# scale.net
KiCad netlist of a schematic drawn in EAGLE
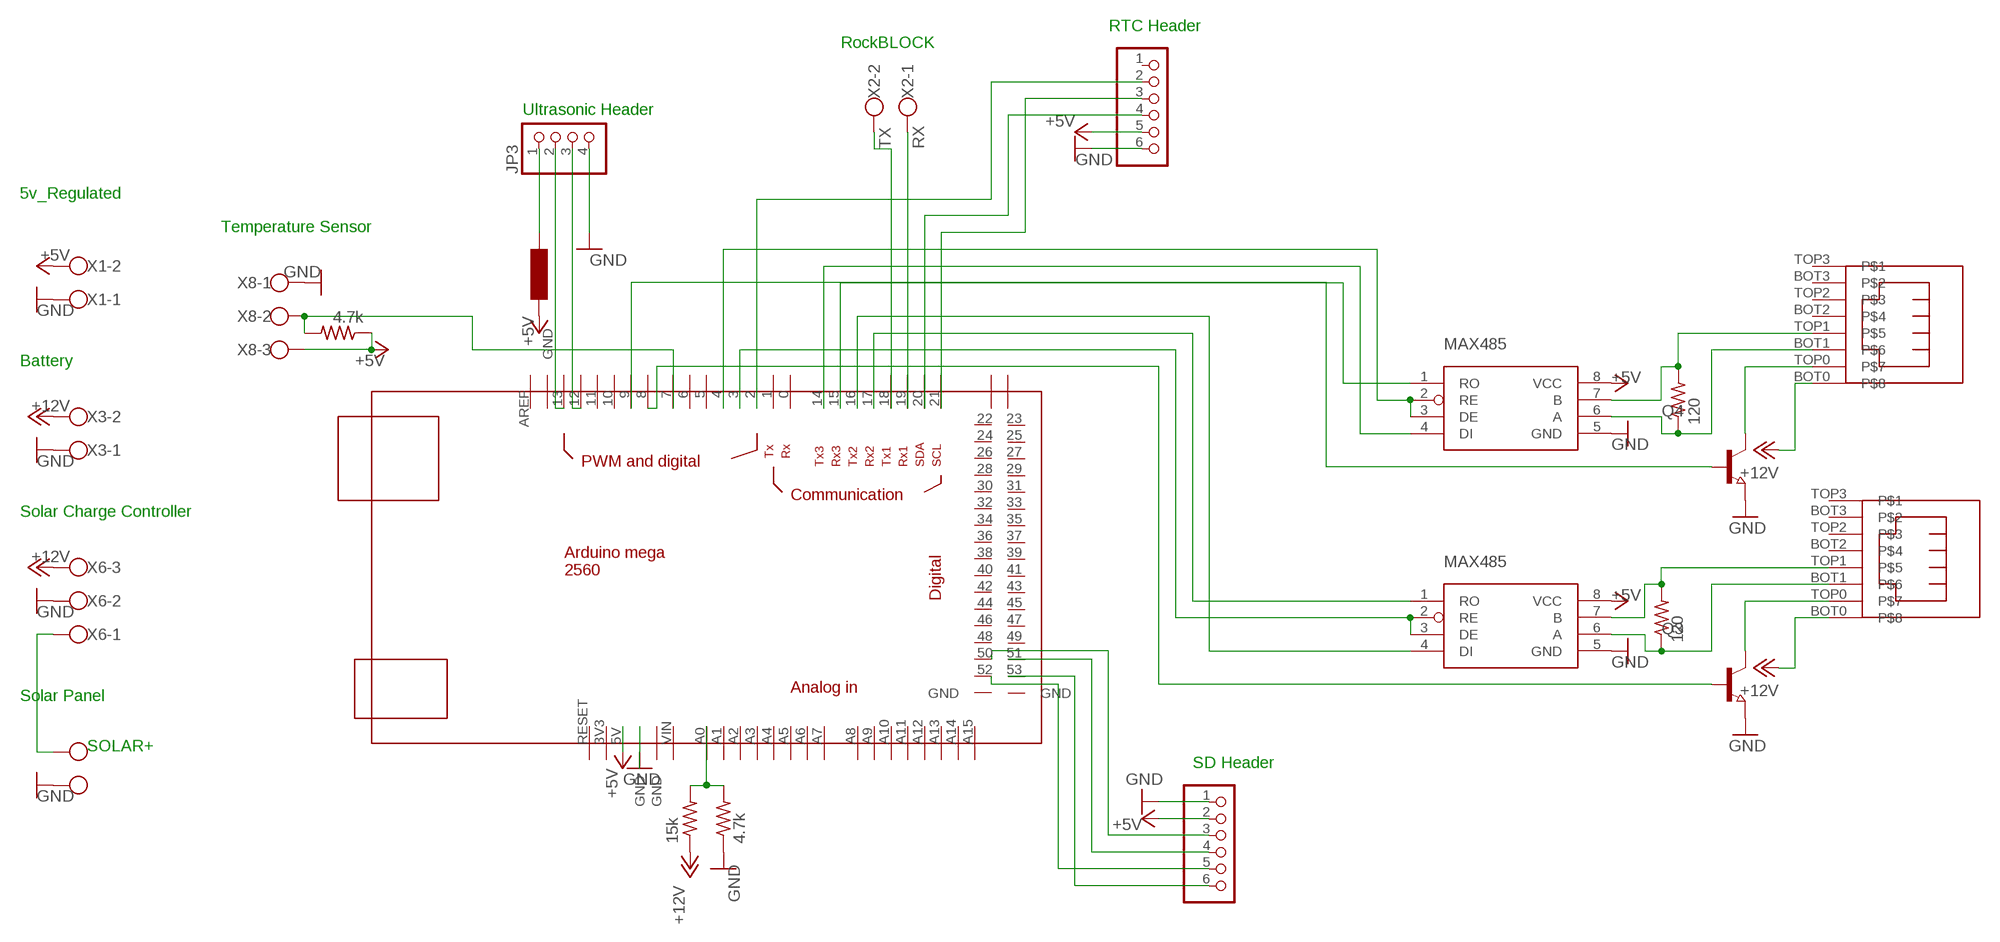
[diagram p0: schematic, sheet 1]

(export (version "E")
  (design (tool "Eeschema 10.0.6"))
  (components
    (comp (ref "JP1")
      (value "PINHD-1X6")
      (footprint "eagle-import:1X06")
      (libsource (lib "eagle-import") (part "PINHD-1X6"))
    )
    (comp (ref "JP2")
      (value "PINHD-1X6")
      (footprint "eagle-import:1X06")
      (libsource (lib "eagle-import") (part "PINHD-1X6"))
    )
    (comp (ref "JP3")
      (value "PINHD-1X4")
      (footprint "eagle-import:1X04")
      (libsource (lib "eagle-import") (part "PINHD-1X4"))
    )
    (comp (ref "JP4")
      (value "ETHERNET")
      (footprint "eagle-import:ETHERNET")
      (libsource (lib "eagle-import") (part "ETHERNET"))
    )
    (comp (ref "JP5")
      (value "ETHERNET")
      (footprint "eagle-import:ETHERNET")
      (libsource (lib "eagle-import") (part "ETHERNET"))
    )
    (comp (ref "L1")
      (value "100uH")
      (footprint "eagle-import:NLFV32T-101K-EF")
      (libsource (lib "eagle-import") (part "NLFV32T-101K-EF"))
    )
    (comp (ref "Q3")
      (value "NPN-TRANSISTOR_SOT23")
      (footprint "eagle-import:SOT23")
      (libsource (lib "eagle-import") (part "NPN-TRANSISTOR_SOT23"))
    )
    (comp (ref "Q4")
      (value "NPN-TRANSISTOR_SOT23")
      (footprint "eagle-import:SOT23")
      (libsource (lib "eagle-import") (part "NPN-TRANSISTOR_SOT23"))
    )
    (comp (ref "R1")
      (value "120")
      (footprint "eagle-import:R0805")
      (libsource (lib "eagle-import") (part "R-US_R0805"))
    )
    (comp (ref "R3")
      (value "4.7k")
      (footprint "eagle-import:R0805")
      (libsource (lib "eagle-import") (part "R-US_R0805"))
    )
    (comp (ref "R7")
      (value "120")
      (footprint "eagle-import:R0805")
      (libsource (lib "eagle-import") (part "R-US_R0805"))
    )
    (comp (ref "R8")
      (value "15k")
      (footprint "eagle-import:R0805")
      (libsource (lib "eagle-import") (part "R-US_R0805"))
    )
    (comp (ref "R9")
      (value "4.7k")
      (footprint "eagle-import:R0805")
      (libsource (lib "eagle-import") (part "R-US_R0805"))
    )
    (comp (ref "U$1")
      (value "MAX485")
      (footprint "eagle-import:SO08")
      (libsource (lib "eagle-import") (part "MAX485"))
    )
    (comp (ref "U$2")
      (value "MAX485")
      (footprint "eagle-import:SO08")
      (libsource (lib "eagle-import") (part "MAX485"))
    )
    (comp (ref "U$3")
      (value "MEGA_DEVICE")
      (footprint "eagle-import:MEGAOUTLINE")
      (libsource (lib "eagle-import") (part "MEGA_DEVICE"))
    )
    (comp (ref "X1")
      (value "W237-102")
      (footprint "eagle-import:W237-102")
      (fields (field (name "MPN") "237-102"))
      (libsource (lib "eagle-import") (part "W237-102"))
    )
    (comp (ref "X2")
      (value "W237-102")
      (footprint "eagle-import:W237-102")
      (fields (field (name "MPN") "237-102"))
      (libsource (lib "eagle-import") (part "W237-102"))
    )
    (comp (ref "X3")
      (value "W237-102")
      (footprint "eagle-import:W237-102")
      (fields (field (name "MPN") "237-102"))
      (libsource (lib "eagle-import") (part "W237-102"))
    )
    (comp (ref "X6")
      (value "W237-103")
      (footprint "eagle-import:W237-103")
      (fields (field (name "MPN") "237-103"))
      (libsource (lib "eagle-import") (part "W237-103"))
    )
    (comp (ref "X7")
      (value "W237-102")
      (footprint "eagle-import:W237-102")
      (fields (field (name "MPN") "237-102"))
      (libsource (lib "eagle-import") (part "W237-102"))
    )
    (comp (ref "X8")
      (value "W237-103")
      (footprint "eagle-import:W237-103")
      (fields (field (name "MPN") "237-103"))
      (libsource (lib "eagle-import") (part "W237-103"))
    )
  )
  (nets
    (net (code "1") (name "+5V") (class "Default")
      (node (ref "JP1") (pin "2") (pinfunction "2_2") (pintype "passive"))
      (node (ref "JP2") (pin "5") (pinfunction "5_5") (pintype "passive"))
      (node (ref "L1") (pin "P$1") (pinfunction "P$1_P$1") (pintype "bidirectional"))
      (node (ref "R3") (pin "1") (pinfunction "1_1") (pintype "passive"))
      (node (ref "U$1") (pin "8") (pinfunction "VCC_8") (pintype "bidirectional"))
      (node (ref "U$2") (pin "8") (pinfunction "VCC_8") (pintype "bidirectional"))
      (node (ref "U$3") (pin "5V") (pinfunction "5V_5V") (pintype "bidirectional"))
      (node (ref "X1") (pin "2") (pinfunction "KL_2") (pintype "passive"))
      (node (ref "X8") (pin "3") (pinfunction "KL_3") (pintype "passive"))
    )
    (net (code "2") (name "+12V") (class "Default")
      (node (ref "JP4") (pin "BOT0") (pinfunction "P$8_BOT0") (pintype "bidirectional"))
      (node (ref "JP5") (pin "BOT0") (pinfunction "P$8_BOT0") (pintype "bidirectional"))
      (node (ref "R8") (pin "1") (pinfunction "1_1") (pintype "passive"))
      (node (ref "X3") (pin "2") (pinfunction "KL_2") (pintype "passive"))
      (node (ref "X6") (pin "3") (pinfunction "KL_3") (pintype "passive"))
    )
    (net (code "3") (name "GND") (class "Default")
      (node (ref "JP1") (pin "1") (pinfunction "1_1") (pintype "passive"))
      (node (ref "JP2") (pin "6") (pinfunction "6_6") (pintype "passive"))
      (node (ref "JP3") (pin "4") (pinfunction "4_4") (pintype "passive"))
      (node (ref "Q3") (pin "2") (pinfunction "E_2") (pintype "passive"))
      (node (ref "Q4") (pin "2") (pinfunction "E_2") (pintype "passive"))
      (node (ref "R9") (pin "1") (pinfunction "1_1") (pintype "passive"))
      (node (ref "U$1") (pin "5") (pinfunction "GND_5") (pintype "bidirectional"))
      (node (ref "U$2") (pin "5") (pinfunction "GND_5") (pintype "bidirectional"))
      (node (ref "U$3") (pin "GND@2") (pinfunction "GND_GND@2") (pintype "bidirectional"))
      (node (ref "X1") (pin "1") (pinfunction "KL_1") (pintype "passive"))
      (node (ref "X3") (pin "1") (pinfunction "KL_1") (pintype "passive"))
      (node (ref "X6") (pin "2") (pinfunction "KL_2") (pintype "passive"))
      (node (ref "X7") (pin "1") (pinfunction "KL_1") (pintype "passive"))
      (node (ref "X8") (pin "1") (pinfunction "KL_1") (pintype "passive"))
    )
    (net (code "4") (name "Net-(JP1-Pad3)") (class "Default")
      (node (ref "JP1") (pin "3") (pinfunction "3_3") (pintype "passive"))
      (node (ref "U$3") (pin "50") (pinfunction "50_50") (pintype "bidirectional"))
    )
    (net (code "5") (name "Net-(JP1-Pad4)") (class "Default")
      (node (ref "JP1") (pin "4") (pinfunction "4_4") (pintype "passive"))
      (node (ref "U$3") (pin "51") (pinfunction "51_51") (pintype "bidirectional"))
    )
    (net (code "6") (name "Net-(JP1-Pad5)") (class "Default")
      (node (ref "JP1") (pin "5") (pinfunction "5_5") (pintype "passive"))
      (node (ref "U$3") (pin "52") (pinfunction "52_52") (pintype "bidirectional"))
    )
    (net (code "7") (name "Net-(JP1-Pad6)") (class "Default")
      (node (ref "JP1") (pin "6") (pinfunction "6_6") (pintype "passive"))
      (node (ref "U$3") (pin "53") (pinfunction "53_53") (pintype "bidirectional"))
    )
    (net (code "8") (name "Net-(JP2-Pad2)") (class "Default")
      (node (ref "JP2") (pin "2") (pinfunction "2_2") (pintype "passive"))
      (node (ref "U$3") (pin "2") (pinfunction "2_2") (pintype "bidirectional"))
    )
    (net (code "9") (name "Net-(JP2-Pad3)") (class "Default")
      (node (ref "JP2") (pin "3") (pinfunction "3_3") (pintype "passive"))
      (node (ref "U$3") (pin "21") (pinfunction "21_21") (pintype "bidirectional"))
    )
    (net (code "10") (name "Net-(JP2-Pad4)") (class "Default")
      (node (ref "JP2") (pin "4") (pinfunction "4_4") (pintype "passive"))
      (node (ref "U$3") (pin "20") (pinfunction "20_20") (pintype "bidirectional"))
    )
    (net (code "11") (name "Net-(JP3-Pad1)") (class "Default")
      (node (ref "JP3") (pin "1") (pinfunction "1_1") (pintype "passive"))
      (node (ref "L1") (pin "P$2") (pinfunction "P$2_P$2") (pintype "bidirectional"))
    )
    (net (code "12") (name "Net-(JP3-Pad2)") (class "Default")
      (node (ref "JP3") (pin "2") (pinfunction "2_2") (pintype "passive"))
      (node (ref "U$3") (pin "13") (pinfunction "13_13") (pintype "bidirectional"))
    )
    (net (code "13") (name "Net-(JP3-Pad3)") (class "Default")
      (node (ref "JP3") (pin "3") (pinfunction "3_3") (pintype "passive"))
      (node (ref "U$3") (pin "12") (pinfunction "12_12") (pintype "bidirectional"))
    )
    (net (code "14") (name "Net-(JP4-P$5)") (class "Default")
      (node (ref "JP4") (pin "TOP1") (pinfunction "P$5_TOP1") (pintype "bidirectional"))
      (node (ref "R1") (pin "2") (pinfunction "2_2") (pintype "passive"))
      (node (ref "U$1") (pin "7") (pinfunction "B_7") (pintype "bidirectional"))
    )
    (net (code "15") (name "Net-(JP4-P$6)") (class "Default")
      (node (ref "JP4") (pin "BOT1") (pinfunction "P$6_BOT1") (pintype "bidirectional"))
      (node (ref "R1") (pin "1") (pinfunction "1_1") (pintype "passive"))
      (node (ref "U$1") (pin "6") (pinfunction "A_6") (pintype "bidirectional"))
    )
    (net (code "16") (name "Net-(JP4-P$7)") (class "Default")
      (node (ref "JP4") (pin "TOP0") (pinfunction "P$7_TOP0") (pintype "bidirectional"))
      (node (ref "Q4") (pin "3") (pinfunction "C_3") (pintype "passive"))
    )
    (net (code "17") (name "Net-(JP5-P$5)") (class "Default")
      (node (ref "JP5") (pin "TOP1") (pinfunction "P$5_TOP1") (pintype "bidirectional"))
      (node (ref "R7") (pin "2") (pinfunction "2_2") (pintype "passive"))
      (node (ref "U$2") (pin "7") (pinfunction "B_7") (pintype "bidirectional"))
    )
    (net (code "18") (name "Net-(JP5-P$6)") (class "Default")
      (node (ref "JP5") (pin "BOT1") (pinfunction "P$6_BOT1") (pintype "bidirectional"))
      (node (ref "R7") (pin "1") (pinfunction "1_1") (pintype "passive"))
      (node (ref "U$2") (pin "6") (pinfunction "A_6") (pintype "bidirectional"))
    )
    (net (code "19") (name "Net-(JP5-P$7)") (class "Default")
      (node (ref "JP5") (pin "TOP0") (pinfunction "P$7_TOP0") (pintype "bidirectional"))
      (node (ref "Q3") (pin "3") (pinfunction "C_3") (pintype "passive"))
    )
    (net (code "20") (name "Net-(Q3-B)") (class "Default")
      (node (ref "Q3") (pin "1") (pinfunction "B_1") (pintype "passive"))
      (node (ref "U$3") (pin "8") (pinfunction "8_8") (pintype "bidirectional"))
    )
    (net (code "21") (name "Net-(Q4-B)") (class "Default")
      (node (ref "Q4") (pin "1") (pinfunction "B_1") (pintype "passive"))
      (node (ref "U$3") (pin "9") (pinfunction "9_9") (pintype "bidirectional"))
    )
    (net (code "22") (name "Net-(R8-Pad2)") (class "Default")
      (node (ref "R8") (pin "2") (pinfunction "2_2") (pintype "passive"))
      (node (ref "R9") (pin "2") (pinfunction "2_2") (pintype "passive"))
      (node (ref "U$3") (pin "A0") (pinfunction "A0_A0") (pintype "bidirectional"))
    )
    (net (code "23") (name "Net-(U$1-DE)") (class "Default")
      (node (ref "U$1") (pin "2") (pinfunction "RE_2") (pintype "bidirectional"))
      (node (ref "U$1") (pin "3") (pinfunction "DE_3") (pintype "bidirectional"))
      (node (ref "U$3") (pin "4") (pinfunction "4_4") (pintype "bidirectional"))
    )
    (net (code "24") (name "Net-(U$1-DI)") (class "Default")
      (node (ref "U$1") (pin "4") (pinfunction "DI_4") (pintype "bidirectional"))
      (node (ref "U$3") (pin "14") (pinfunction "14_14") (pintype "bidirectional"))
    )
    (net (code "25") (name "Net-(U$1-RO)") (class "Default")
      (node (ref "U$1") (pin "1") (pinfunction "RO_1") (pintype "bidirectional"))
      (node (ref "U$3") (pin "15") (pinfunction "15_15") (pintype "bidirectional"))
    )
    (net (code "26") (name "Net-(U$2-DE)") (class "Default")
      (node (ref "U$2") (pin "2") (pinfunction "RE_2") (pintype "bidirectional"))
      (node (ref "U$2") (pin "3") (pinfunction "DE_3") (pintype "bidirectional"))
      (node (ref "U$3") (pin "3") (pinfunction "3_3") (pintype "bidirectional"))
    )
    (net (code "27") (name "Net-(U$2-DI)") (class "Default")
      (node (ref "U$2") (pin "4") (pinfunction "DI_4") (pintype "bidirectional"))
      (node (ref "U$3") (pin "16") (pinfunction "16_16") (pintype "bidirectional"))
    )
    (net (code "28") (name "Net-(U$2-RO)") (class "Default")
      (node (ref "U$2") (pin "1") (pinfunction "RO_1") (pintype "bidirectional"))
      (node (ref "U$3") (pin "17") (pinfunction "17_17") (pintype "bidirectional"))
    )
    (net (code "29") (name "Net-(X2A-KL)") (class "Default")
      (node (ref "U$3") (pin "19") (pinfunction "19_19") (pintype "bidirectional"))
      (node (ref "X2") (pin "1") (pinfunction "KL_1") (pintype "passive"))
    )
    (net (code "30") (name "Net-(X2B-KL)") (class "Default")
      (node (ref "U$3") (pin "18") (pinfunction "18_18") (pintype "bidirectional"))
      (node (ref "X2") (pin "2") (pinfunction "KL_2") (pintype "passive"))
    )
    (net (code "31") (name "Net-(X6A-KL)") (class "Default")
      (node (ref "X6") (pin "1") (pinfunction "KL_1") (pintype "passive"))
      (node (ref "X7") (pin "2") (pinfunction "KL_2") (pintype "passive"))
    )
    (net (code "32") (name "Net-(X8B-KL)") (class "Default")
      (node (ref "R3") (pin "2") (pinfunction "2_2") (pintype "passive"))
      (node (ref "U$3") (pin "7") (pinfunction "7_7") (pintype "bidirectional"))
      (node (ref "X8") (pin "2") (pinfunction "KL_2") (pintype "passive"))
    )
    (net (code "33") (name "unconnected-(JP2-Pad1)") (class "Default")
      (node (ref "JP2") (pin "1") (pinfunction "1_1") (pintype "passive"))
    )
    (net (code "34") (name "unconnected-(JP4-P$1-PadTOP3)") (class "Default")
      (node (ref "JP4") (pin "TOP3") (pinfunction "P$1_TOP3") (pintype "bidirectional"))
    )
    (net (code "35") (name "unconnected-(JP4-P$2-PadBOT3)") (class "Default")
      (node (ref "JP4") (pin "BOT3") (pinfunction "P$2_BOT3") (pintype "bidirectional"))
    )
    (net (code "36") (name "unconnected-(JP4-P$3-PadTOP2)") (class "Default")
      (node (ref "JP4") (pin "TOP2") (pinfunction "P$3_TOP2") (pintype "bidirectional"))
    )
    (net (code "37") (name "unconnected-(JP4-P$4-PadBOT2)") (class "Default")
      (node (ref "JP4") (pin "BOT2") (pinfunction "P$4_BOT2") (pintype "bidirectional"))
    )
    (net (code "38") (name "unconnected-(JP5-P$1-PadTOP3)") (class "Default")
      (node (ref "JP5") (pin "TOP3") (pinfunction "P$1_TOP3") (pintype "bidirectional"))
    )
    (net (code "39") (name "unconnected-(JP5-P$2-PadBOT3)") (class "Default")
      (node (ref "JP5") (pin "BOT3") (pinfunction "P$2_BOT3") (pintype "bidirectional"))
    )
    (net (code "40") (name "unconnected-(JP5-P$3-PadTOP2)") (class "Default")
      (node (ref "JP5") (pin "TOP2") (pinfunction "P$3_TOP2") (pintype "bidirectional"))
    )
    (net (code "41") (name "unconnected-(JP5-P$4-PadBOT2)") (class "Default")
      (node (ref "JP5") (pin "BOT2") (pinfunction "P$4_BOT2") (pintype "bidirectional"))
    )
    (net (code "42") (name "unconnected-(U$3-5V-PadGND@4)") (class "Default")
      (node (ref "U$3") (pin "GND@4") (pinfunction "5V_GND@4") (pintype "bidirectional"))
    )
    (net (code "43") (name "unconnected-(U$3-5V-PadGND@5)") (class "Default")
      (node (ref "U$3") (pin "GND@5") (pinfunction "5V_GND@5") (pintype "bidirectional"))
    )
    (net (code "44") (name "unconnected-(U$3-GND-PadGND@1)") (class "Default")
      (node (ref "U$3") (pin "GND@1") (pinfunction "GND_GND@1") (pintype "bidirectional"))
    )
    (net (code "45") (name "unconnected-(U$3-GND-PadGND@3)") (class "Default")
      (node (ref "U$3") (pin "GND@3") (pinfunction "GND_GND@3") (pintype "bidirectional"))
    )
    (net (code "46") (name "unconnected-(U$3-GND-PadGND@6)") (class "Default")
      (node (ref "U$3") (pin "GND@6") (pinfunction "GND_GND@6") (pintype "bidirectional"))
    )
    (net (code "47") (name "unconnected-(U$3-GND-PadGND@7)") (class "Default")
      (node (ref "U$3") (pin "GND@7") (pinfunction "GND_GND@7") (pintype "bidirectional"))
    )
    (net (code "48") (name "unconnected-(U$3-Pad0)") (class "Default")
      (node (ref "U$3") (pin "0") (pinfunction "0_0") (pintype "bidirectional"))
    )
    (net (code "49") (name "unconnected-(U$3-Pad1)") (class "Default")
      (node (ref "U$3") (pin "1") (pinfunction "1_1") (pintype "bidirectional"))
    )
    (net (code "50") (name "unconnected-(U$3-Pad3V3)") (class "Default")
      (node (ref "U$3") (pin "3V3") (pinfunction "3V3_3V3") (pintype "bidirectional"))
    )
    (net (code "51") (name "unconnected-(U$3-Pad5)") (class "Default")
      (node (ref "U$3") (pin "5") (pinfunction "5_5") (pintype "bidirectional"))
    )
    (net (code "52") (name "unconnected-(U$3-Pad6)") (class "Default")
      (node (ref "U$3") (pin "6") (pinfunction "6_6") (pintype "bidirectional"))
    )
    (net (code "53") (name "unconnected-(U$3-Pad10)") (class "Default")
      (node (ref "U$3") (pin "10") (pinfunction "10_10") (pintype "bidirectional"))
    )
    (net (code "54") (name "unconnected-(U$3-Pad11)") (class "Default")
      (node (ref "U$3") (pin "11") (pinfunction "11_11") (pintype "bidirectional"))
    )
    (net (code "55") (name "unconnected-(U$3-Pad22)") (class "Default")
      (node (ref "U$3") (pin "22") (pinfunction "22_22") (pintype "bidirectional"))
    )
    (net (code "56") (name "unconnected-(U$3-Pad23)") (class "Default")
      (node (ref "U$3") (pin "23") (pinfunction "23_23") (pintype "bidirectional"))
    )
    (net (code "57") (name "unconnected-(U$3-Pad24)") (class "Default")
      (node (ref "U$3") (pin "24") (pinfunction "24_24") (pintype "bidirectional"))
    )
    (net (code "58") (name "unconnected-(U$3-Pad25)") (class "Default")
      (node (ref "U$3") (pin "25") (pinfunction "25_25") (pintype "bidirectional"))
    )
    (net (code "59") (name "unconnected-(U$3-Pad26)") (class "Default")
      (node (ref "U$3") (pin "26") (pinfunction "26_26") (pintype "bidirectional"))
    )
    (net (code "60") (name "unconnected-(U$3-Pad27)") (class "Default")
      (node (ref "U$3") (pin "27") (pinfunction "27_27") (pintype "bidirectional"))
    )
    (net (code "61") (name "unconnected-(U$3-Pad28)") (class "Default")
      (node (ref "U$3") (pin "28") (pinfunction "28_28") (pintype "bidirectional"))
    )
    (net (code "62") (name "unconnected-(U$3-Pad29)") (class "Default")
      (node (ref "U$3") (pin "29") (pinfunction "29_29") (pintype "bidirectional"))
    )
    (net (code "63") (name "unconnected-(U$3-Pad30)") (class "Default")
      (node (ref "U$3") (pin "30") (pinfunction "30_30") (pintype "bidirectional"))
    )
    (net (code "64") (name "unconnected-(U$3-Pad31)") (class "Default")
      (node (ref "U$3") (pin "31") (pinfunction "31_31") (pintype "bidirectional"))
    )
    (net (code "65") (name "unconnected-(U$3-Pad32)") (class "Default")
      (node (ref "U$3") (pin "32") (pinfunction "32_32") (pintype "bidirectional"))
    )
    (net (code "66") (name "unconnected-(U$3-Pad33)") (class "Default")
      (node (ref "U$3") (pin "33") (pinfunction "33_33") (pintype "bidirectional"))
    )
    (net (code "67") (name "unconnected-(U$3-Pad34)") (class "Default")
      (node (ref "U$3") (pin "34") (pinfunction "34_34") (pintype "bidirectional"))
    )
    (net (code "68") (name "unconnected-(U$3-Pad35)") (class "Default")
      (node (ref "U$3") (pin "35") (pinfunction "35_35") (pintype "bidirectional"))
    )
    (net (code "69") (name "unconnected-(U$3-Pad36)") (class "Default")
      (node (ref "U$3") (pin "36") (pinfunction "36_36") (pintype "bidirectional"))
    )
    (net (code "70") (name "unconnected-(U$3-Pad37)") (class "Default")
      (node (ref "U$3") (pin "37") (pinfunction "37_37") (pintype "bidirectional"))
    )
    (net (code "71") (name "unconnected-(U$3-Pad38)") (class "Default")
      (node (ref "U$3") (pin "38") (pinfunction "38_38") (pintype "bidirectional"))
    )
    (net (code "72") (name "unconnected-(U$3-Pad39)") (class "Default")
      (node (ref "U$3") (pin "39") (pinfunction "39_39") (pintype "bidirectional"))
    )
    (net (code "73") (name "unconnected-(U$3-Pad40)") (class "Default")
      (node (ref "U$3") (pin "40") (pinfunction "40_40") (pintype "bidirectional"))
    )
    (net (code "74") (name "unconnected-(U$3-Pad41)") (class "Default")
      (node (ref "U$3") (pin "41") (pinfunction "41_41") (pintype "bidirectional"))
    )
    (net (code "75") (name "unconnected-(U$3-Pad42)") (class "Default")
      (node (ref "U$3") (pin "42") (pinfunction "42_42") (pintype "bidirectional"))
    )
    (net (code "76") (name "unconnected-(U$3-Pad43)") (class "Default")
      (node (ref "U$3") (pin "43") (pinfunction "43_43") (pintype "bidirectional"))
    )
    (net (code "77") (name "unconnected-(U$3-Pad44)") (class "Default")
      (node (ref "U$3") (pin "44") (pinfunction "44_44") (pintype "bidirectional"))
    )
    (net (code "78") (name "unconnected-(U$3-Pad45)") (class "Default")
      (node (ref "U$3") (pin "45") (pinfunction "45_45") (pintype "bidirectional"))
    )
    (net (code "79") (name "unconnected-(U$3-Pad46)") (class "Default")
      (node (ref "U$3") (pin "46") (pinfunction "46_46") (pintype "bidirectional"))
    )
    (net (code "80") (name "unconnected-(U$3-Pad47)") (class "Default")
      (node (ref "U$3") (pin "47") (pinfunction "47_47") (pintype "bidirectional"))
    )
    (net (code "81") (name "unconnected-(U$3-Pad48)") (class "Default")
      (node (ref "U$3") (pin "48") (pinfunction "48_48") (pintype "bidirectional"))
    )
    (net (code "82") (name "unconnected-(U$3-Pad49)") (class "Default")
      (node (ref "U$3") (pin "49") (pinfunction "49_49") (pintype "bidirectional"))
    )
    (net (code "83") (name "unconnected-(U$3-PadA1)") (class "Default")
      (node (ref "U$3") (pin "A1") (pinfunction "A1_A1") (pintype "bidirectional"))
    )
    (net (code "84") (name "unconnected-(U$3-PadA2)") (class "Default")
      (node (ref "U$3") (pin "A2") (pinfunction "A2_A2") (pintype "bidirectional"))
    )
    (net (code "85") (name "unconnected-(U$3-PadA3)") (class "Default")
      (node (ref "U$3") (pin "A3") (pinfunction "A3_A3") (pintype "bidirectional"))
    )
    (net (code "86") (name "unconnected-(U$3-PadA4)") (class "Default")
      (node (ref "U$3") (pin "A4") (pinfunction "A4_A4") (pintype "bidirectional"))
    )
    (net (code "87") (name "unconnected-(U$3-PadA5)") (class "Default")
      (node (ref "U$3") (pin "A5") (pinfunction "A5_A5") (pintype "bidirectional"))
    )
    (net (code "88") (name "unconnected-(U$3-PadA6)") (class "Default")
      (node (ref "U$3") (pin "A6") (pinfunction "A6_A6") (pintype "bidirectional"))
    )
    (net (code "89") (name "unconnected-(U$3-PadA7)") (class "Default")
      (node (ref "U$3") (pin "A7") (pinfunction "A7_A7") (pintype "bidirectional"))
    )
    (net (code "90") (name "unconnected-(U$3-PadA8)") (class "Default")
      (node (ref "U$3") (pin "A8") (pinfunction "A8_A8") (pintype "bidirectional"))
    )
    (net (code "91") (name "unconnected-(U$3-PadA9)") (class "Default")
      (node (ref "U$3") (pin "A9") (pinfunction "A9_A9") (pintype "bidirectional"))
    )
    (net (code "92") (name "unconnected-(U$3-PadA10)") (class "Default")
      (node (ref "U$3") (pin "A10") (pinfunction "A10_A10") (pintype "bidirectional"))
    )
    (net (code "93") (name "unconnected-(U$3-PadA11)") (class "Default")
      (node (ref "U$3") (pin "A11") (pinfunction "A11_A11") (pintype "bidirectional"))
    )
    (net (code "94") (name "unconnected-(U$3-PadA12)") (class "Default")
      (node (ref "U$3") (pin "A12") (pinfunction "A12_A12") (pintype "bidirectional"))
    )
    (net (code "95") (name "unconnected-(U$3-PadA13)") (class "Default")
      (node (ref "U$3") (pin "A13") (pinfunction "A13_A13") (pintype "bidirectional"))
    )
    (net (code "96") (name "unconnected-(U$3-PadA14)") (class "Default")
      (node (ref "U$3") (pin "A14") (pinfunction "A14_A14") (pintype "bidirectional"))
    )
    (net (code "97") (name "unconnected-(U$3-PadA15)") (class "Default")
      (node (ref "U$3") (pin "A15") (pinfunction "A15_A15") (pintype "bidirectional"))
    )
    (net (code "98") (name "unconnected-(U$3-PadAREF)") (class "Default")
      (node (ref "U$3") (pin "AREF") (pinfunction "AREF_AREF") (pintype "bidirectional"))
    )
    (net (code "99") (name "unconnected-(U$3-PadRESET)") (class "Default")
      (node (ref "U$3") (pin "RESET") (pinfunction "RESET_RESET") (pintype "bidirectional"))
    )
    (net (code "100") (name "unconnected-(U$3-PadVIN)") (class "Default")
      (node (ref "U$3") (pin "VIN") (pinfunction "VIN_VIN") (pintype "bidirectional"))
    )
  )
)
